# touch.net
KiCad netlist of a schematic drawn in EAGLE
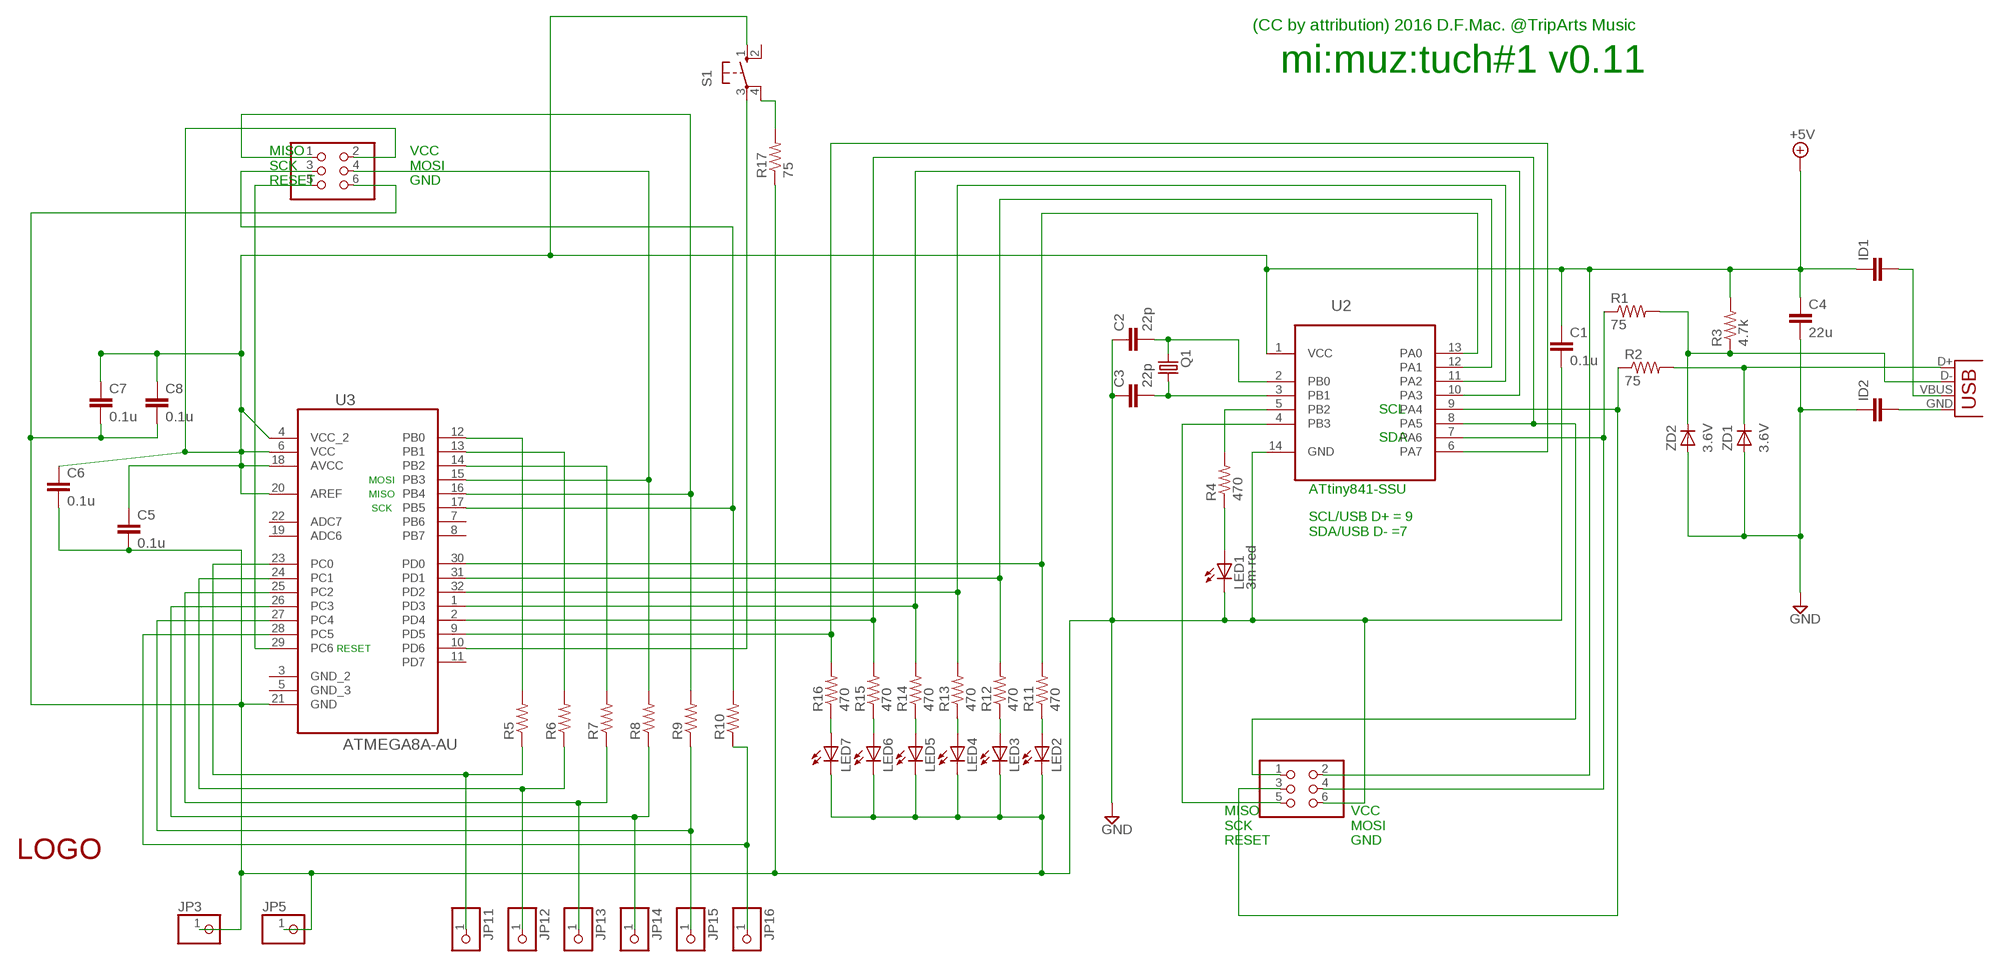
[diagram p0: schematic, sheet 1]

(export (version "E")
  (design (tool "Eeschema 10.0.6"))
  (components
    (comp (ref "C1")
      (value "0.1u")
      (footprint "eagle-import:C0603")
      (libsource (lib "eagle-import") (part "C-EUC0603"))
    )
    (comp (ref "C2")
      (value "22p")
      (footprint "eagle-import:C0603")
      (libsource (lib "eagle-import") (part "C-EUC0603"))
    )
    (comp (ref "C3")
      (value "22p")
      (footprint "eagle-import:C0603")
      (libsource (lib "eagle-import") (part "C-EUC0603"))
    )
    (comp (ref "C4")
      (value "22u")
      (footprint "eagle-import:C0805")
      (libsource (lib "eagle-import") (part "C-EUC0805"))
    )
    (comp (ref "C5")
      (value "0.1u")
      (footprint "eagle-import:C0603")
      (libsource (lib "eagle-import") (part "C-EUC0603"))
    )
    (comp (ref "C6")
      (value "0.1u")
      (footprint "eagle-import:C0603")
      (libsource (lib "eagle-import") (part "C-EUC0603"))
    )
    (comp (ref "C7")
      (value "0.1u")
      (footprint "eagle-import:C0603")
      (libsource (lib "eagle-import") (part "C-EUC0603"))
    )
    (comp (ref "C8")
      (value "0.1u")
      (footprint "eagle-import:C0603")
      (libsource (lib "eagle-import") (part "C-EUC0603"))
    )
    (comp (ref "ID1")
      (value "C-EUC0805")
      (footprint "eagle-import:C0805")
      (libsource (lib "eagle-import") (part "C-EUC0805"))
    )
    (comp (ref "ID2")
      (value "C-EUC0805")
      (footprint "eagle-import:C0805")
      (libsource (lib "eagle-import") (part "C-EUC0805"))
    )
    (comp (ref "JP1")
      (value "PINHD-2X3")
      (footprint "eagle-import:2X03")
      (libsource (lib "eagle-import") (part "PINHD-2X3"))
    )
    (comp (ref "JP2")
      (value "PINHD-2X3")
      (footprint "eagle-import:2X03")
      (libsource (lib "eagle-import") (part "PINHD-2X3"))
    )
    (comp (ref "JP3")
      (value "PINHD-1X13MM")
      (footprint "eagle-import:1X01")
      (libsource (lib "eagle-import") (part "PINHD-1X13MM"))
    )
    (comp (ref "JP4")
      (value "USB-MICROB")
      (footprint "eagle-import:USB-MICROB")
      (libsource (lib "eagle-import") (part "USB-MICROB"))
    )
    (comp (ref "JP5")
      (value "PINHD-1X13MM")
      (footprint "eagle-import:1X01")
      (libsource (lib "eagle-import") (part "PINHD-1X13MM"))
    )
    (comp (ref "JP11")
      (value "PINHD-1X15MM")
      (footprint "eagle-import:1X01-LARGE")
      (libsource (lib "eagle-import") (part "PINHD-1X15MM"))
    )
    (comp (ref "JP12")
      (value "PINHD-1X15MM")
      (footprint "eagle-import:1X01-LARGE")
      (libsource (lib "eagle-import") (part "PINHD-1X15MM"))
    )
    (comp (ref "JP13")
      (value "PINHD-1X15MM")
      (footprint "eagle-import:1X01-LARGE")
      (libsource (lib "eagle-import") (part "PINHD-1X15MM"))
    )
    (comp (ref "JP14")
      (value "PINHD-1X15MM")
      (footprint "eagle-import:1X01-LARGE")
      (libsource (lib "eagle-import") (part "PINHD-1X15MM"))
    )
    (comp (ref "JP15")
      (value "PINHD-1X15MM")
      (footprint "eagle-import:1X01-LARGE")
      (libsource (lib "eagle-import") (part "PINHD-1X15MM"))
    )
    (comp (ref "JP16")
      (value "PINHD-1X15MM")
      (footprint "eagle-import:1X01-LARGE")
      (libsource (lib "eagle-import") (part "PINHD-1X15MM"))
    )
    (comp (ref "LED1")
      (value "3m-red")
      (footprint "eagle-import:LED3MM")
      (libsource (lib "eagle-import") (part "LED3MM"))
    )
    (comp (ref "LED2")
      (value "LED3MM")
      (footprint "eagle-import:LED3MM")
      (libsource (lib "eagle-import") (part "LED3MM"))
    )
    (comp (ref "LED3")
      (value "LED3MM")
      (footprint "eagle-import:LED3MM")
      (libsource (lib "eagle-import") (part "LED3MM"))
    )
    (comp (ref "LED4")
      (value "LED3MM")
      (footprint "eagle-import:LED3MM")
      (libsource (lib "eagle-import") (part "LED3MM"))
    )
    (comp (ref "LED5")
      (value "LED3MM")
      (footprint "eagle-import:LED3MM")
      (libsource (lib "eagle-import") (part "LED3MM"))
    )
    (comp (ref "LED6")
      (value "LED3MM")
      (footprint "eagle-import:LED3MM")
      (libsource (lib "eagle-import") (part "LED3MM"))
    )
    (comp (ref "LED7")
      (value "LED3MM")
      (footprint "eagle-import:LED3MM")
      (libsource (lib "eagle-import") (part "LED3MM"))
    )
    (comp (ref "Q1")
      (value "MC-405")
      (footprint "eagle-import:MC-405")
      (libsource (lib "eagle-import") (part "MC-405"))
    )
    (comp (ref "R1")
      (value "75")
      (footprint "eagle-import:R0603")
      (libsource (lib "eagle-import") (part "R-US_R0603"))
    )
    (comp (ref "R2")
      (value "75")
      (footprint "eagle-import:R0603")
      (libsource (lib "eagle-import") (part "R-US_R0603"))
    )
    (comp (ref "R3")
      (value "4.7k")
      (footprint "eagle-import:R0603")
      (libsource (lib "eagle-import") (part "R-US_R0603"))
    )
    (comp (ref "R4")
      (value "470")
      (footprint "eagle-import:R0603")
      (libsource (lib "eagle-import") (part "R-US_R0603"))
    )
    (comp (ref "R5")
      (value "R-US_R0805")
      (footprint "eagle-import:R0805")
      (libsource (lib "eagle-import") (part "R-US_R0805"))
    )
    (comp (ref "R6")
      (value "R-US_R0805")
      (footprint "eagle-import:R0805")
      (libsource (lib "eagle-import") (part "R-US_R0805"))
    )
    (comp (ref "R7")
      (value "R-US_R0805")
      (footprint "eagle-import:R0805")
      (libsource (lib "eagle-import") (part "R-US_R0805"))
    )
    (comp (ref "R8")
      (value "R-US_R0805")
      (footprint "eagle-import:R0805")
      (libsource (lib "eagle-import") (part "R-US_R0805"))
    )
    (comp (ref "R9")
      (value "R-US_R0805")
      (footprint "eagle-import:R0805")
      (libsource (lib "eagle-import") (part "R-US_R0805"))
    )
    (comp (ref "R10")
      (value "R-US_R0805")
      (footprint "eagle-import:R0805")
      (libsource (lib "eagle-import") (part "R-US_R0805"))
    )
    (comp (ref "R11")
      (value "470")
      (footprint "eagle-import:R0603")
      (libsource (lib "eagle-import") (part "R-US_R0603"))
    )
    (comp (ref "R12")
      (value "470")
      (footprint "eagle-import:R0603")
      (libsource (lib "eagle-import") (part "R-US_R0603"))
    )
    (comp (ref "R13")
      (value "470")
      (footprint "eagle-import:R0603")
      (libsource (lib "eagle-import") (part "R-US_R0603"))
    )
    (comp (ref "R14")
      (value "470")
      (footprint "eagle-import:R0603")
      (libsource (lib "eagle-import") (part "R-US_R0603"))
    )
    (comp (ref "R15")
      (value "470")
      (footprint "eagle-import:R0603")
      (libsource (lib "eagle-import") (part "R-US_R0603"))
    )
    (comp (ref "R16")
      (value "470")
      (footprint "eagle-import:R0603")
      (libsource (lib "eagle-import") (part "R-US_R0603"))
    )
    (comp (ref "R17")
      (value "75")
      (footprint "eagle-import:R0603")
      (libsource (lib "eagle-import") (part "R-US_R0603"))
    )
    (comp (ref "S1")
      (value "10-XX")
      (footprint "eagle-import:B3F-10XX")
      (fields (field (name "MPN") "B3F-1000"))
      (libsource (lib "eagle-import") (part "10-XX"))
    )
    (comp (ref "U$1")
      (value "LOGOSMALL")
      (footprint "eagle-import:LOGO-SMALL")
      (libsource (lib "eagle-import") (part "LOGOSMALL"))
    )
    (comp (ref "U2")
      (value "ATTINY44-20SSU")
      (footprint "eagle-import:SOIC127P600X175-14N")
      (libsource (lib "eagle-import") (part "ATTINY44-20SSU"))
    )
    (comp (ref "U3")
      (value "ATMEGA8A-AU")
      (footprint "eagle-import:QFP80P900X900X120-32N")
      (libsource (lib "eagle-import") (part "ATMEGA8A-AU"))
    )
    (comp (ref "ZD1")
      (value "3.6V")
      (footprint "eagle-import:SOD323-W")
      (libsource (lib "eagle-import") (part "DIODE-SOD323-W"))
    )
    (comp (ref "ZD2")
      (value "3.6V")
      (footprint "eagle-import:SOD323-W")
      (libsource (lib "eagle-import") (part "DIODE-SOD323-W"))
    )
  )
  (nets
    (net (code "1") (name "+5V") (class "Default")
      (node (ref "C1") (pin "1") (pinfunction "1_1") (pintype "passive"))
      (node (ref "C4") (pin "1") (pinfunction "1_1") (pintype "passive"))
      (node (ref "C5") (pin "1") (pinfunction "1_1") (pintype "passive"))
      (node (ref "C6") (pin "1") (pinfunction "1_1") (pintype "passive"))
      (node (ref "C7") (pin "1") (pinfunction "1_1") (pintype "passive"))
      (node (ref "C8") (pin "1") (pinfunction "1_1") (pintype "passive"))
      (node (ref "ID1") (pin "1") (pinfunction "1_1") (pintype "passive"))
      (node (ref "JP1") (pin "2") (pinfunction "2_2") (pintype "passive"))
      (node (ref "JP2") (pin "2") (pinfunction "2_2") (pintype "passive"))
      (node (ref "R3") (pin "2") (pinfunction "2_2") (pintype "passive"))
      (node (ref "S1") (pin "1") (pinfunction "S_1") (pintype "passive"))
      (node (ref "U2") (pin "1") (pinfunction "VCC_1") (pintype "power_in"))
      (node (ref "U3") (pin "18") (pinfunction "AVCC_18") (pintype "power_in"))
      (node (ref "U3") (pin "20") (pinfunction "AREF_20") (pintype "input"))
      (node (ref "U3") (pin "4") (pinfunction "VCC_2_4") (pintype "power_in"))
      (node (ref "U3") (pin "6") (pinfunction "VCC_6") (pintype "power_in"))
    )
    (net (code "2") (name "GND") (class "Default")
      (node (ref "C1") (pin "2") (pinfunction "2_2") (pintype "passive"))
      (node (ref "C2") (pin "1") (pinfunction "1_1") (pintype "passive"))
      (node (ref "C3") (pin "1") (pinfunction "1_1") (pintype "passive"))
      (node (ref "C4") (pin "2") (pinfunction "2_2") (pintype "passive"))
      (node (ref "C5") (pin "2") (pinfunction "2_2") (pintype "passive"))
      (node (ref "C6") (pin "2") (pinfunction "2_2") (pintype "passive"))
      (node (ref "C7") (pin "2") (pinfunction "2_2") (pintype "passive"))
      (node (ref "C8") (pin "2") (pinfunction "2_2") (pintype "passive"))
      (node (ref "ID2") (pin "1") (pinfunction "1_1") (pintype "passive"))
      (node (ref "JP1") (pin "6") (pinfunction "6_6") (pintype "passive"))
      (node (ref "JP2") (pin "6") (pinfunction "6_6") (pintype "passive"))
      (node (ref "JP3") (pin "1") (pinfunction "1_1") (pintype "passive"))
      (node (ref "JP5") (pin "1") (pinfunction "1_1") (pintype "passive"))
      (node (ref "LED1") (pin "K") (pinfunction "C_K") (pintype "passive"))
      (node (ref "LED2") (pin "K") (pinfunction "C_K") (pintype "passive"))
      (node (ref "LED3") (pin "K") (pinfunction "C_K") (pintype "passive"))
      (node (ref "LED4") (pin "K") (pinfunction "C_K") (pintype "passive"))
      (node (ref "LED5") (pin "K") (pinfunction "C_K") (pintype "passive"))
      (node (ref "LED6") (pin "K") (pinfunction "C_K") (pintype "passive"))
      (node (ref "LED7") (pin "K") (pinfunction "C_K") (pintype "passive"))
      (node (ref "R17") (pin "1") (pinfunction "1_1") (pintype "passive"))
      (node (ref "U2") (pin "14") (pinfunction "GND_14") (pintype "passive"))
      (node (ref "U3") (pin "21") (pinfunction "GND_21") (pintype "passive"))
      (node (ref "ZD1") (pin "A") (pinfunction "A_A") (pintype "passive"))
      (node (ref "ZD2") (pin "A") (pinfunction "A_A") (pintype "passive"))
    )
    (net (code "3") (name "Net-(ID1-Pad2)") (class "Default")
      (node (ref "ID1") (pin "2") (pinfunction "2_2") (pintype "passive"))
      (node (ref "JP4") (pin "VBUS") (pinfunction "VBUS_VBUS") (pintype "bidirectional"))
    )
    (net (code "4") (name "Net-(ID2-Pad2)") (class "Default")
      (node (ref "ID2") (pin "2") (pinfunction "2_2") (pintype "passive"))
      (node (ref "JP4") (pin "GND") (pinfunction "GND_GND") (pintype "bidirectional"))
    )
    (net (code "5") (name "Net-(JP4-PadD+)") (class "Default")
      (node (ref "JP4") (pin "D+") (pinfunction "D+_D+") (pintype "bidirectional"))
      (node (ref "R2") (pin "2") (pinfunction "2_2") (pintype "passive"))
      (node (ref "ZD1") (pin "C") (pinfunction "C_C") (pintype "passive"))
    )
    (net (code "6") (name "Net-(JP4-PadD-)") (class "Default")
      (node (ref "JP4") (pin "D-") (pinfunction "D-_D-") (pintype "bidirectional"))
      (node (ref "R1") (pin "2") (pinfunction "2_2") (pintype "passive"))
      (node (ref "R3") (pin "1") (pinfunction "1_1") (pintype "passive"))
      (node (ref "ZD2") (pin "C") (pinfunction "C_C") (pintype "passive"))
    )
    (net (code "7") (name "Net-(LED1-PadA)") (class "Default")
      (node (ref "LED1") (pin "A") (pinfunction "A_A") (pintype "passive"))
      (node (ref "R4") (pin "1") (pinfunction "1_1") (pintype "passive"))
    )
    (net (code "8") (name "Net-(LED2-PadA)") (class "Default")
      (node (ref "LED2") (pin "A") (pinfunction "A_A") (pintype "passive"))
      (node (ref "R11") (pin "1") (pinfunction "1_1") (pintype "passive"))
    )
    (net (code "9") (name "Net-(LED3-PadA)") (class "Default")
      (node (ref "LED3") (pin "A") (pinfunction "A_A") (pintype "passive"))
      (node (ref "R12") (pin "1") (pinfunction "1_1") (pintype "passive"))
    )
    (net (code "10") (name "Net-(LED4-PadA)") (class "Default")
      (node (ref "LED4") (pin "A") (pinfunction "A_A") (pintype "passive"))
      (node (ref "R13") (pin "1") (pinfunction "1_1") (pintype "passive"))
    )
    (net (code "11") (name "Net-(LED5-PadA)") (class "Default")
      (node (ref "LED5") (pin "A") (pinfunction "A_A") (pintype "passive"))
      (node (ref "R14") (pin "1") (pinfunction "1_1") (pintype "passive"))
    )
    (net (code "12") (name "Net-(LED6-PadA)") (class "Default")
      (node (ref "LED6") (pin "A") (pinfunction "A_A") (pintype "passive"))
      (node (ref "R15") (pin "1") (pinfunction "1_1") (pintype "passive"))
    )
    (net (code "13") (name "Net-(LED7-PadA)") (class "Default")
      (node (ref "LED7") (pin "A") (pinfunction "A_A") (pintype "passive"))
      (node (ref "R16") (pin "1") (pinfunction "1_1") (pintype "passive"))
    )
    (net (code "14") (name "Net-(S1-P)") (class "Default")
      (node (ref "S1") (pin "3") (pinfunction "P_3") (pintype "passive"))
      (node (ref "U3") (pin "10") (pinfunction "PD6_10") (pintype "passive"))
    )
    (net (code "15") (name "Net-(S1-P1)") (class "Default")
      (node (ref "R17") (pin "2") (pinfunction "2_2") (pintype "passive"))
      (node (ref "S1") (pin "4") (pinfunction "P1_4") (pintype "passive"))
    )
    (net (code "16") (name "Net-(U2-PA0)") (class "Default")
      (node (ref "R11") (pin "2") (pinfunction "2_2") (pintype "passive"))
      (node (ref "U2") (pin "13") (pinfunction "PA0_13") (pintype "bidirectional"))
      (node (ref "U3") (pin "30") (pinfunction "PD0_30") (pintype "bidirectional"))
    )
    (net (code "17") (name "Net-(U2-PA1)") (class "Default")
      (node (ref "R12") (pin "2") (pinfunction "2_2") (pintype "passive"))
      (node (ref "U2") (pin "12") (pinfunction "PA1_12") (pintype "bidirectional"))
      (node (ref "U3") (pin "31") (pinfunction "PD1_31") (pintype "bidirectional"))
    )
    (net (code "18") (name "Net-(U2-PA2)") (class "Default")
      (node (ref "R13") (pin "2") (pinfunction "2_2") (pintype "passive"))
      (node (ref "U2") (pin "11") (pinfunction "PA2_11") (pintype "bidirectional"))
      (node (ref "U3") (pin "32") (pinfunction "PD2_32") (pintype "bidirectional"))
    )
    (net (code "19") (name "Net-(U2-PA3)") (class "Default")
      (node (ref "R14") (pin "2") (pinfunction "2_2") (pintype "passive"))
      (node (ref "U2") (pin "10") (pinfunction "PA3_10") (pintype "bidirectional"))
      (node (ref "U3") (pin "1") (pinfunction "PD3_1") (pintype "bidirectional"))
    )
    (net (code "20") (name "Net-(U2-PA4)") (class "Default")
      (node (ref "JP2") (pin "3") (pinfunction "3_3") (pintype "passive"))
      (node (ref "R2") (pin "1") (pinfunction "1_1") (pintype "passive"))
      (node (ref "U2") (pin "9") (pinfunction "PA4_9") (pintype "bidirectional"))
    )
    (net (code "21") (name "Net-(U2-PA5)") (class "Default")
      (node (ref "JP2") (pin "1") (pinfunction "1_1") (pintype "passive"))
      (node (ref "R15") (pin "2") (pinfunction "2_2") (pintype "passive"))
      (node (ref "U2") (pin "8") (pinfunction "PA5_8") (pintype "bidirectional"))
      (node (ref "U3") (pin "2") (pinfunction "PD4_2") (pintype "bidirectional"))
    )
    (net (code "22") (name "Net-(U2-PA6)") (class "Default")
      (node (ref "JP2") (pin "4") (pinfunction "4_4") (pintype "passive"))
      (node (ref "R1") (pin "1") (pinfunction "1_1") (pintype "passive"))
      (node (ref "U2") (pin "7") (pinfunction "PA6_7") (pintype "bidirectional"))
    )
    (net (code "23") (name "Net-(U2-PA7)") (class "Default")
      (node (ref "R16") (pin "2") (pinfunction "2_2") (pintype "passive"))
      (node (ref "U2") (pin "6") (pinfunction "PA7_6") (pintype "bidirectional"))
      (node (ref "U3") (pin "9") (pinfunction "PD5_9") (pintype "passive"))
    )
    (net (code "24") (name "Net-(U2-PB0)") (class "Default")
      (node (ref "C2") (pin "2") (pinfunction "2_2") (pintype "passive"))
      (node (ref "Q1") (pin "2") (pinfunction "2_2") (pintype "passive"))
      (node (ref "U2") (pin "2") (pinfunction "PB0_2") (pintype "bidirectional"))
    )
    (net (code "25") (name "Net-(U2-PB1)") (class "Default")
      (node (ref "C3") (pin "2") (pinfunction "2_2") (pintype "passive"))
      (node (ref "Q1") (pin "1") (pinfunction "1_1") (pintype "passive"))
      (node (ref "U2") (pin "3") (pinfunction "PB1_3") (pintype "bidirectional"))
    )
    (net (code "26") (name "Net-(U2-PB2)") (class "Default")
      (node (ref "R4") (pin "2") (pinfunction "2_2") (pintype "passive"))
      (node (ref "U2") (pin "5") (pinfunction "PB2_5") (pintype "bidirectional"))
    )
    (net (code "27") (name "Net-(U2-PB3)") (class "Default")
      (node (ref "JP2") (pin "5") (pinfunction "5_5") (pintype "passive"))
      (node (ref "U2") (pin "4") (pinfunction "PB3_4") (pintype "bidirectional"))
    )
    (net (code "28") (name "Net-(U3-PB0)") (class "Default")
      (node (ref "R5") (pin "2") (pinfunction "2_2") (pintype "passive"))
      (node (ref "U3") (pin "12") (pinfunction "PB0_12") (pintype "passive"))
    )
    (net (code "29") (name "Net-(U3-PB1)") (class "Default")
      (node (ref "R6") (pin "2") (pinfunction "2_2") (pintype "passive"))
      (node (ref "U3") (pin "13") (pinfunction "PB1_13") (pintype "passive"))
    )
    (net (code "30") (name "Net-(U3-PB2)") (class "Default")
      (node (ref "R7") (pin "2") (pinfunction "2_2") (pintype "passive"))
      (node (ref "U3") (pin "14") (pinfunction "PB2_14") (pintype "passive"))
    )
    (net (code "31") (name "Net-(U3-PB3)") (class "Default")
      (node (ref "JP1") (pin "4") (pinfunction "4_4") (pintype "passive"))
      (node (ref "R8") (pin "2") (pinfunction "2_2") (pintype "passive"))
      (node (ref "U3") (pin "15") (pinfunction "PB3_15") (pintype "passive"))
    )
    (net (code "32") (name "Net-(U3-PB4)") (class "Default")
      (node (ref "JP1") (pin "1") (pinfunction "1_1") (pintype "passive"))
      (node (ref "R9") (pin "2") (pinfunction "2_2") (pintype "passive"))
      (node (ref "U3") (pin "16") (pinfunction "PB4_16") (pintype "passive"))
    )
    (net (code "33") (name "Net-(U3-PB5)") (class "Default")
      (node (ref "JP1") (pin "3") (pinfunction "3_3") (pintype "passive"))
      (node (ref "R10") (pin "2") (pinfunction "2_2") (pintype "passive"))
      (node (ref "U3") (pin "17") (pinfunction "PB5_17") (pintype "passive"))
    )
    (net (code "34") (name "Net-(U3-PC0)") (class "Default")
      (node (ref "JP11") (pin "1") (pinfunction "1_1") (pintype "passive"))
      (node (ref "R5") (pin "1") (pinfunction "1_1") (pintype "passive"))
      (node (ref "U3") (pin "23") (pinfunction "PC0_23") (pintype "bidirectional"))
    )
    (net (code "35") (name "Net-(U3-PC1)") (class "Default")
      (node (ref "JP12") (pin "1") (pinfunction "1_1") (pintype "passive"))
      (node (ref "R6") (pin "1") (pinfunction "1_1") (pintype "passive"))
      (node (ref "U3") (pin "24") (pinfunction "PC1_24") (pintype "bidirectional"))
    )
    (net (code "36") (name "Net-(U3-PC2)") (class "Default")
      (node (ref "JP13") (pin "1") (pinfunction "1_1") (pintype "passive"))
      (node (ref "R7") (pin "1") (pinfunction "1_1") (pintype "passive"))
      (node (ref "U3") (pin "25") (pinfunction "PC2_25") (pintype "bidirectional"))
    )
    (net (code "37") (name "Net-(U3-PC3)") (class "Default")
      (node (ref "JP14") (pin "1") (pinfunction "1_1") (pintype "passive"))
      (node (ref "R8") (pin "1") (pinfunction "1_1") (pintype "passive"))
      (node (ref "U3") (pin "26") (pinfunction "PC3_26") (pintype "bidirectional"))
    )
    (net (code "38") (name "Net-(U3-PC4)") (class "Default")
      (node (ref "JP15") (pin "1") (pinfunction "1_1") (pintype "passive"))
      (node (ref "R9") (pin "1") (pinfunction "1_1") (pintype "passive"))
      (node (ref "U3") (pin "27") (pinfunction "PC4_27") (pintype "bidirectional"))
    )
    (net (code "39") (name "Net-(U3-PC5)") (class "Default")
      (node (ref "JP16") (pin "1") (pinfunction "1_1") (pintype "passive"))
      (node (ref "R10") (pin "1") (pinfunction "1_1") (pintype "passive"))
      (node (ref "U3") (pin "28") (pinfunction "PC5_28") (pintype "bidirectional"))
    )
    (net (code "40") (name "Net-(U3-PC6)") (class "Default")
      (node (ref "JP1") (pin "5") (pinfunction "5_5") (pintype "passive"))
      (node (ref "U3") (pin "29") (pinfunction "PC6_29") (pintype "bidirectional"))
    )
    (net (code "41") (name "unconnected-(S1-S1-Pad2)") (class "Default")
      (node (ref "S1") (pin "2") (pinfunction "S1_2") (pintype "passive"))
    )
    (net (code "42") (name "unconnected-(U3-ADC6-Pad19)") (class "Default")
      (node (ref "U3") (pin "19") (pinfunction "ADC6_19") (pintype "input"))
    )
    (net (code "43") (name "unconnected-(U3-ADC7-Pad22)") (class "Default")
      (node (ref "U3") (pin "22") (pinfunction "ADC7_22") (pintype "input"))
    )
    (net (code "44") (name "unconnected-(U3-GND_2-Pad3)") (class "Default")
      (node (ref "U3") (pin "3") (pinfunction "GND_2_3") (pintype "passive"))
    )
    (net (code "45") (name "unconnected-(U3-GND_3-Pad5)") (class "Default")
      (node (ref "U3") (pin "5") (pinfunction "GND_3_5") (pintype "passive"))
    )
    (net (code "46") (name "unconnected-(U3-PB6-Pad7)") (class "Default")
      (node (ref "U3") (pin "7") (pinfunction "PB6_7") (pintype "bidirectional"))
    )
    (net (code "47") (name "unconnected-(U3-PB7-Pad8)") (class "Default")
      (node (ref "U3") (pin "8") (pinfunction "PB7_8") (pintype "passive"))
    )
    (net (code "48") (name "unconnected-(U3-PD7-Pad11)") (class "Default")
      (node (ref "U3") (pin "11") (pinfunction "PD7_11") (pintype "passive"))
    )
  )
)
